# ultra-violet-tooth-sensor-mk-2_1.net
KiCad netlist of a schematic drawn in EAGLE
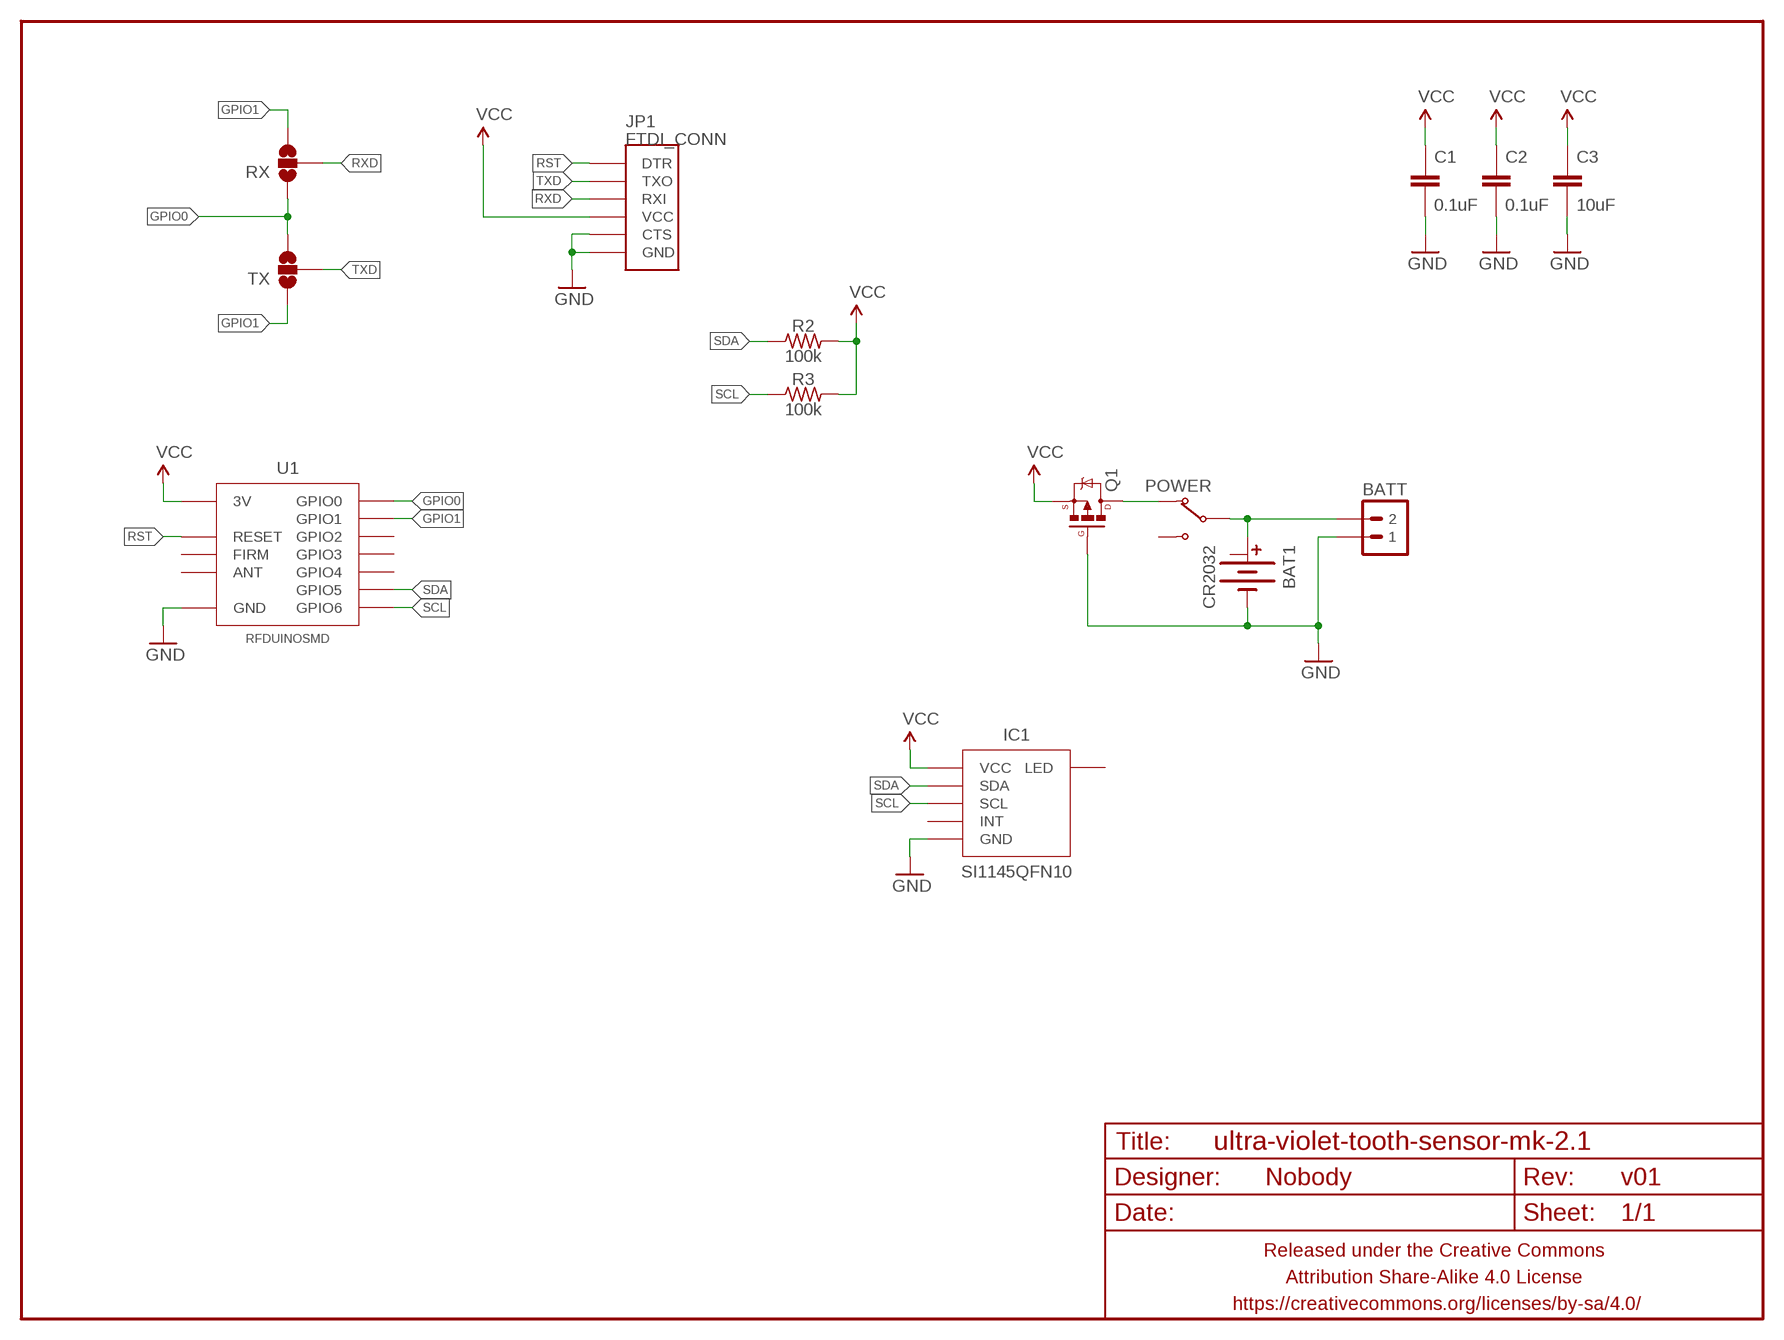
[diagram p0: schematic, sheet 1]

(export (version "E")
  (design (tool "Eeschema 10.0.6"))
  (components
    (comp (ref "BAT1")
      (value "CR2032")
      (footprint "eagle-import:BATTCON_20MM_MINE_STAHPIT")
      (libsource (lib "eagle-import") (part "BATTERY-COINCR2032_SMD_TIGHT"))
    )
    (comp (ref "BATT")
      (value "M02PTH-CENTERED-R+")
      (footprint "eagle-import:1X02-CENTER-R+")
      (libsource (lib "eagle-import") (part "M02PTH-CENTERED-R+"))
    )
    (comp (ref "C1")
      (value "0.1uF")
      (footprint "eagle-import:C0805")
      (libsource (lib "eagle-import") (part "CAPACITOR-CERAMICC0805"))
    )
    (comp (ref "C2")
      (value "0.1uF")
      (footprint "eagle-import:C0805")
      (libsource (lib "eagle-import") (part "CAPACITOR-CERAMICC0805"))
    )
    (comp (ref "C3")
      (value "10uF")
      (footprint "eagle-import:C1206")
      (libsource (lib "eagle-import") (part "CAPACITOR-CERAMICC1206"))
    )
    (comp (ref "FRAME1")
      (value "FRAME-LETTERNO_PACKAGE")
      (footprint "eagle-import:DUMMY")
      (fields (field (name "DESIGNER") "Nobody"))
      (libsource (lib "eagle-import") (part "FRAME-LETTERNO_PACKAGE"))
    )
    (comp (ref "IC1")
      (value "SI1145QFN10")
      (footprint "eagle-import:SI1145")
      (libsource (lib "eagle-import") (part "SI1145QFN10"))
    )
    (comp (ref "JP1")
      (value "FTDI_CONN")
      (footprint "eagle-import:FTDI_CONN")
      (libsource (lib "eagle-import") (part "FTDI_CONN"))
    )
    (comp (ref "POWER")
      (value "SWITCH-SPDTPTH-RA-2.54MM")
      (footprint "eagle-import:SPDT-RA-2.54MM")
      (libsource (lib "eagle-import") (part "SWITCH-SPDTPTH-RA-2.54MM"))
    )
    (comp (ref "Q1")
      (value "MOSFET-PCHANNELIRLML2244")
      (footprint "eagle-import:SOT23-3")
      (libsource (lib "eagle-import") (part "MOSFET-PCHANNELIRLML2244"))
    )
    (comp (ref "R2")
      (value "100k")
      (footprint "eagle-import:R0805")
      (libsource (lib "eagle-import") (part "RESISTORR0805"))
    )
    (comp (ref "R3")
      (value "100k")
      (footprint "eagle-import:R0805")
      (libsource (lib "eagle-import") (part "RESISTORR0805"))
    )
    (comp (ref "RX")
      (value "JUMPER-PAD-3-NOFULL_BOX_SILK")
      (footprint "eagle-import:PAD-JUMPER-3-NO_YES_SILK_FULL_BOX")
      (libsource (lib "eagle-import") (part "JUMPER-PAD-3-NOFULL_BOX_SILK"))
    )
    (comp (ref "TX")
      (value "JUMPER-PAD-3-NOFULL_BOX_SILK")
      (footprint "eagle-import:PAD-JUMPER-3-NO_YES_SILK_FULL_BOX")
      (libsource (lib "eagle-import") (part "JUMPER-PAD-3-NOFULL_BOX_SILK"))
    )
    (comp (ref "U1")
      (value "RFDUINOSMD")
      (footprint "eagle-import:RFDUINO-SMD")
      (libsource (lib "eagle-import") (part "RFDUINOSMD"))
    )
  )
  (nets
    (net (code "1") (name "GND") (class "Default")
      (node (ref "BAT1") (pin "BOTTOM") (pinfunction "-_BOTTOM") (pintype "bidirectional"))
      (node (ref "BATT") (pin "1") (pinfunction "1_1") (pintype "passive"))
      (node (ref "C1") (pin "2") (pinfunction "2_2") (pintype "passive"))
      (node (ref "C2") (pin "2") (pinfunction "2_2") (pintype "passive"))
      (node (ref "C3") (pin "2") (pinfunction "2_2") (pintype "passive"))
      (node (ref "IC1") (pin "GND") (pinfunction "GND_GND") (pintype "bidirectional"))
      (node (ref "JP1") (pin "CTS") (pinfunction "CTS_CTS") (pintype "bidirectional"))
      (node (ref "JP1") (pin "GND") (pinfunction "GND_GND") (pintype "bidirectional"))
      (node (ref "Q1") (pin "1") (pinfunction "G_1") (pintype "passive"))
      (node (ref "U1") (pin "GND@1") (pinfunction "GND_GND@1") (pintype "bidirectional"))
      (node (ref "U1") (pin "GND@2") (pinfunction "GND_GND@2") (pintype "bidirectional"))
      (node (ref "U1") (pin "GND@3") (pinfunction "GND_GND@3") (pintype "bidirectional"))
      (node (ref "U1") (pin "GND@4") (pinfunction "GND_GND@4") (pintype "bidirectional"))
      (node (ref "U1") (pin "GND@5") (pinfunction "GND_GND@5") (pintype "bidirectional"))
      (node (ref "U1") (pin "GND@6") (pinfunction "GND_GND@6") (pintype "bidirectional"))
      (node (ref "U1") (pin "GND@7") (pinfunction "GND_GND@7") (pintype "bidirectional"))
      (node (ref "U1") (pin "GND@8") (pinfunction "GND_GND@8") (pintype "bidirectional"))
    )
    (net (code "2") (name "GPIO0") (class "Default")
      (node (ref "RX") (pin "1") (pinfunction "1_1") (pintype "passive"))
      (node (ref "TX") (pin "3") (pinfunction "3_3") (pintype "passive"))
      (node (ref "U1") (pin "GPIO0") (pinfunction "GPIO0_GPIO0") (pintype "bidirectional"))
    )
    (net (code "3") (name "GPIO1") (class "Default")
      (node (ref "RX") (pin "3") (pinfunction "3_3") (pintype "passive"))
      (node (ref "TX") (pin "1") (pinfunction "1_1") (pintype "passive"))
      (node (ref "U1") (pin "GPIO1") (pinfunction "GPIO1_GPIO1") (pintype "bidirectional"))
    )
    (net (code "4") (name "Net-(BAT1-+)") (class "Default")
      (node (ref "BAT1") (pin "TOP@1") (pinfunction "+_TOP@1") (pintype "bidirectional"))
      (node (ref "BATT") (pin "2") (pinfunction "2_2") (pintype "passive"))
      (node (ref "POWER") (pin "2") (pinfunction "COM_2") (pintype "passive"))
    )
    (net (code "5") (name "Net-(POWER-NC)") (class "Default")
      (node (ref "POWER") (pin "1") (pinfunction "NC_1") (pintype "passive"))
      (node (ref "Q1") (pin "3") (pinfunction "D_3") (pintype "passive"))
    )
    (net (code "6") (name "RST") (class "Default")
      (node (ref "JP1") (pin "DTR") (pinfunction "DTR_DTR") (pintype "bidirectional"))
      (node (ref "U1") (pin "RESET") (pinfunction "RESET_RESET") (pintype "bidirectional"))
    )
    (net (code "7") (name "RXD") (class "Default")
      (node (ref "JP1") (pin "RXI") (pinfunction "RXI_RXI") (pintype "bidirectional"))
      (node (ref "RX") (pin "2") (pinfunction "2_2") (pintype "passive"))
    )
    (net (code "8") (name "SCL") (class "Default")
      (node (ref "IC1") (pin "SCL") (pinfunction "SCL_SCL") (pintype "bidirectional"))
      (node (ref "R3") (pin "1") (pinfunction "1_1") (pintype "passive"))
      (node (ref "U1") (pin "GPIO6") (pinfunction "GPIO6_GPIO6") (pintype "bidirectional"))
    )
    (net (code "9") (name "SDA") (class "Default")
      (node (ref "IC1") (pin "SDA") (pinfunction "SDA_SDA") (pintype "bidirectional"))
      (node (ref "R2") (pin "1") (pinfunction "1_1") (pintype "passive"))
      (node (ref "U1") (pin "GPIO5") (pinfunction "GPIO5_GPIO5") (pintype "bidirectional"))
    )
    (net (code "10") (name "TXD") (class "Default")
      (node (ref "JP1") (pin "TXO") (pinfunction "TXO_TXO") (pintype "bidirectional"))
      (node (ref "TX") (pin "2") (pinfunction "2_2") (pintype "passive"))
    )
    (net (code "11") (name "VCC") (class "Default")
      (node (ref "C1") (pin "1") (pinfunction "1_1") (pintype "passive"))
      (node (ref "C2") (pin "1") (pinfunction "1_1") (pintype "passive"))
      (node (ref "C3") (pin "1") (pinfunction "1_1") (pintype "passive"))
      (node (ref "IC1") (pin "VCC@1") (pinfunction "VCC_VCC@1") (pintype "bidirectional"))
      (node (ref "IC1") (pin "VCC@2") (pinfunction "VCC_VCC@2") (pintype "bidirectional"))
      (node (ref "IC1") (pin "VCC@3") (pinfunction "VCC_VCC@3") (pintype "bidirectional"))
      (node (ref "JP1") (pin "VCC") (pinfunction "VCC_VCC") (pintype "bidirectional"))
      (node (ref "Q1") (pin "2") (pinfunction "S_2") (pintype "passive"))
      (node (ref "R2") (pin "2") (pinfunction "2_2") (pintype "passive"))
      (node (ref "R3") (pin "2") (pinfunction "2_2") (pintype "passive"))
      (node (ref "U1") (pin "3V") (pinfunction "3V_3V") (pintype "bidirectional"))
    )
    (net (code "12") (name "unconnected-(BAT1-+1-PadTOP@2)") (class "Default")
      (node (ref "BAT1") (pin "TOP@2") (pinfunction "+1_TOP@2") (pintype "bidirectional"))
    )
    (net (code "13") (name "unconnected-(IC1-PadINT)") (class "Default")
      (node (ref "IC1") (pin "INT") (pinfunction "INT_INT") (pintype "bidirectional"))
    )
    (net (code "14") (name "unconnected-(IC1-PadLED)") (class "Default")
      (node (ref "IC1") (pin "LED") (pinfunction "LED_LED") (pintype "bidirectional"))
    )
    (net (code "15") (name "unconnected-(POWER-NO-Pad3)") (class "Default")
      (node (ref "POWER") (pin "3") (pinfunction "NO_3") (pintype "passive"))
    )
    (net (code "16") (name "unconnected-(U1-FIRM-PadFACTORY)") (class "Default")
      (node (ref "U1") (pin "FACTORY") (pinfunction "FIRM_FACTORY") (pintype "bidirectional"))
    )
    (net (code "17") (name "unconnected-(U1-PadANT)") (class "Default")
      (node (ref "U1") (pin "ANT") (pinfunction "ANT_ANT") (pintype "bidirectional"))
    )
    (net (code "18") (name "unconnected-(U1-PadGPIO2)") (class "Default")
      (node (ref "U1") (pin "GPIO2") (pinfunction "GPIO2_GPIO2") (pintype "bidirectional"))
    )
    (net (code "19") (name "unconnected-(U1-PadGPIO3)") (class "Default")
      (node (ref "U1") (pin "GPIO3") (pinfunction "GPIO3_GPIO3") (pintype "bidirectional"))
    )
    (net (code "20") (name "unconnected-(U1-PadGPIO4)") (class "Default")
      (node (ref "U1") (pin "GPIO4") (pinfunction "GPIO4_GPIO4") (pintype "bidirectional"))
    )
  )
)
